# CONNECTORS.net
KiCad netlist of a schematic drawn in Altium Designer
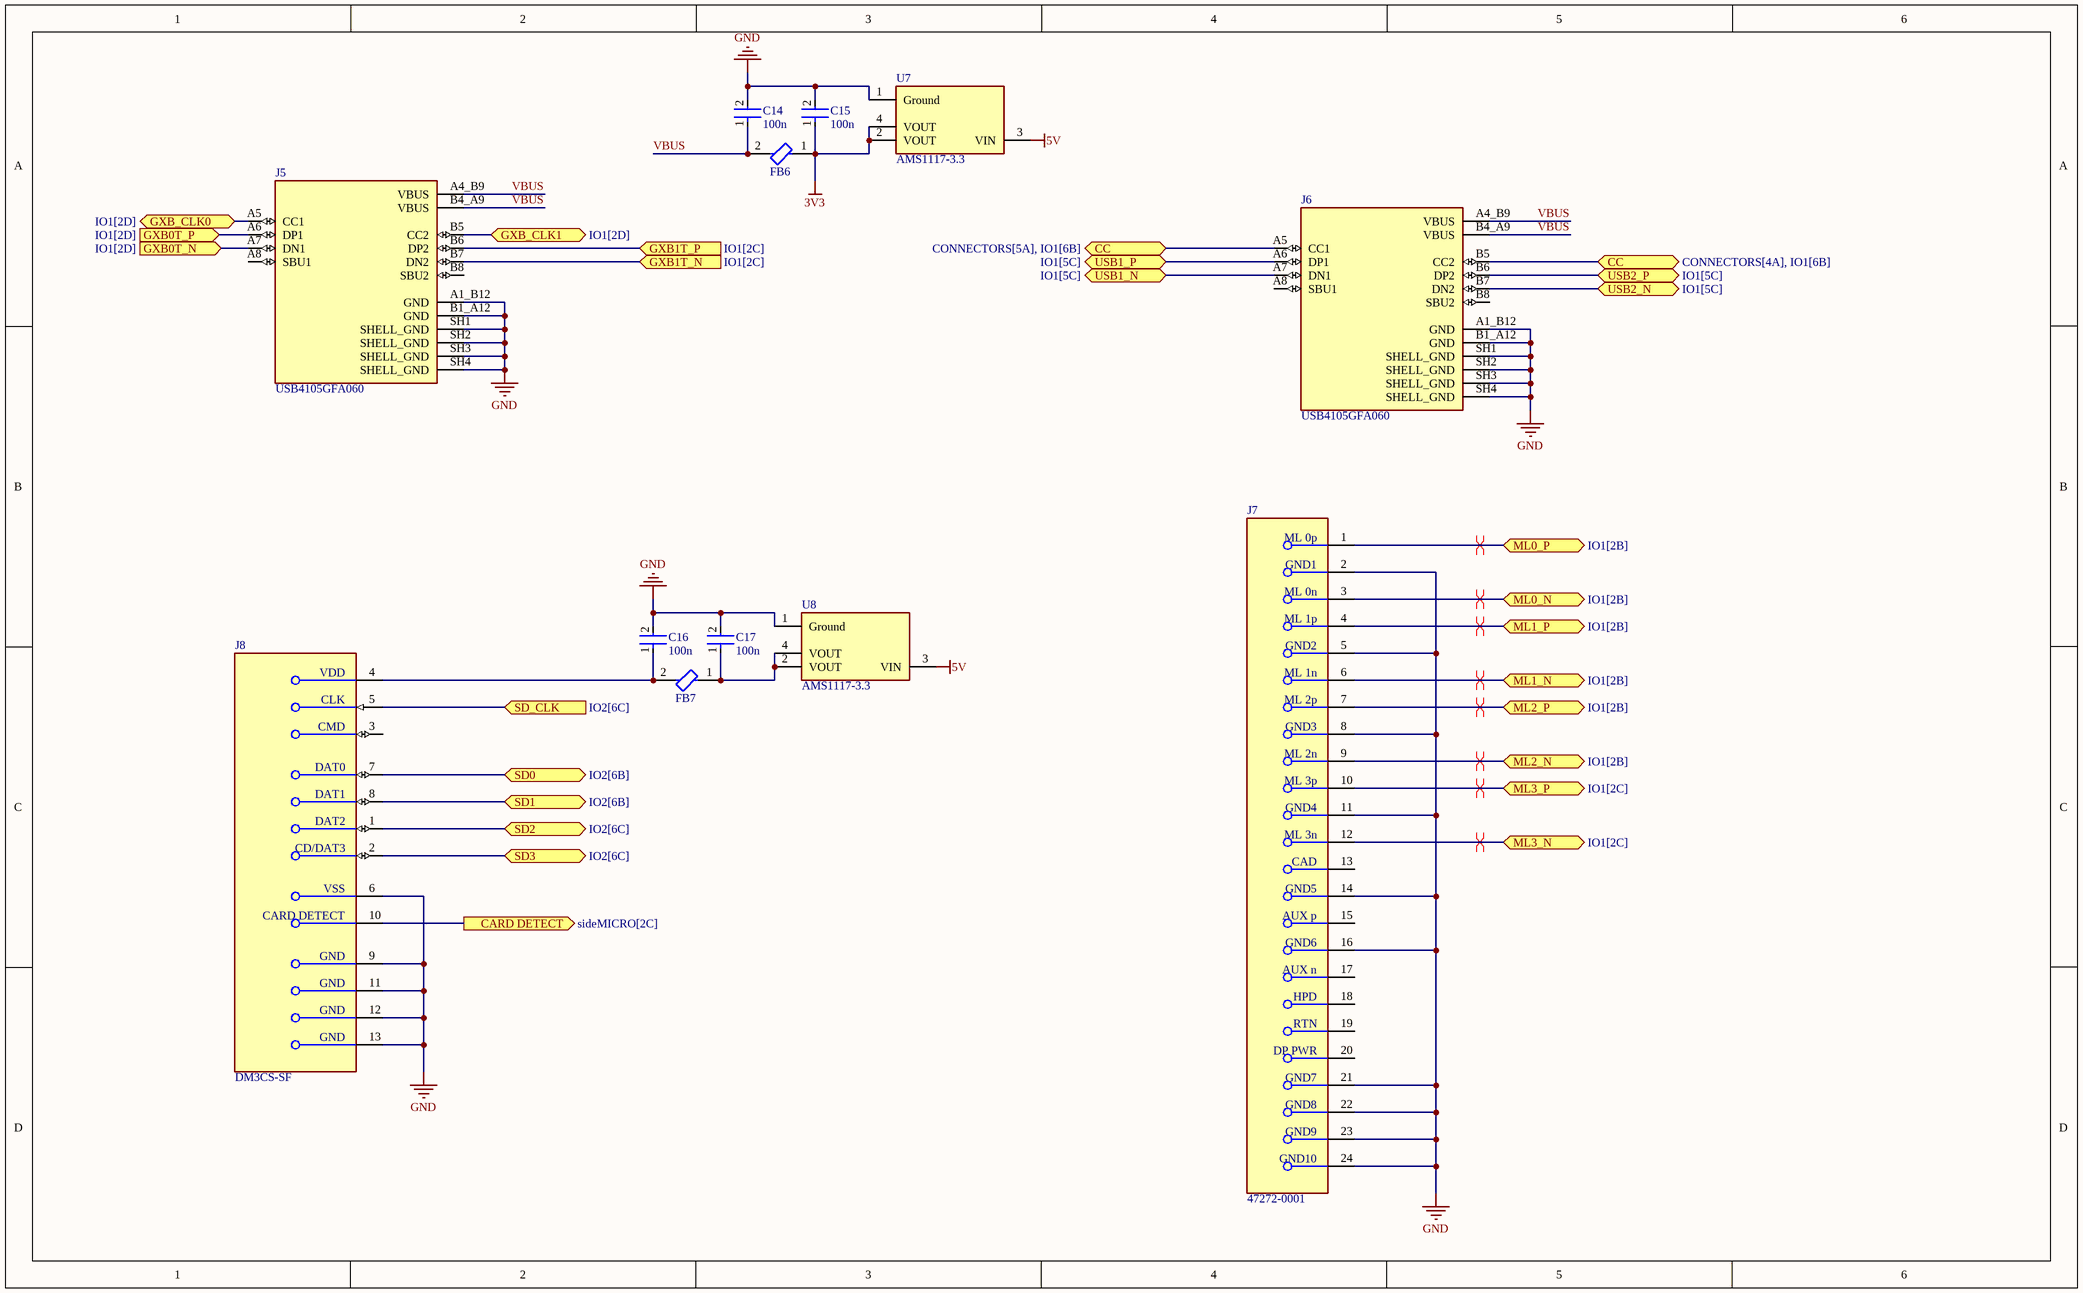
[diagram p0: CONNECTORS.SchDoc]

(export (version "E")
  (design (tool "Eeschema 10.0.6"))
  (components
    (comp (ref "C14")
      (value "100n")
      (footprint "FP-CL10-IPC_C")
      (description "Cap Ceramic 4.7uF 10V X5R ±10% Pad SMD 0603 +85°C T/R")
      (fields (field (name "TOLERANCE") "10%"))
      (libsource (lib "Altium Content Vault") (part "b4654b650e69147ec39a6b967a45e02"))
    )
    (comp (ref "C15")
      (value "100n")
      (footprint "FP-CL10-IPC_C")
      (description "Cap Ceramic 4.7uF 10V X5R ±10% Pad SMD 0603 +85°C T/R")
      (fields (field (name "TOLERANCE") "10%"))
      (libsource (lib "Altium Content Vault") (part "b4654b650e69147ec39a6b967a45e02"))
    )
    (comp (ref "C16")
      (value "100n")
      (footprint "FP-CL10-IPC_C")
      (description "Cap Ceramic 4.7uF 10V X5R ±10% Pad SMD 0603 +85°C T/R")
      (fields (field (name "TOLERANCE") "10%"))
      (libsource (lib "Altium Content Vault") (part "b4654b650e69147ec39a6b967a45e02"))
    )
    (comp (ref "C17")
      (value "100n")
      (footprint "FP-CL10-IPC_C")
      (description "Cap Ceramic 4.7uF 10V X5R ±10% Pad SMD 0603 +85°C T/R")
      (fields (field (name "TOLERANCE") "10%"))
      (libsource (lib "Altium Content Vault") (part "b4654b650e69147ec39a6b967a45e02"))
    )
    (comp (ref "FB6")
      (value "BLM18KG121TN1D")
      (footprint "FP-BLM18-0_15-t0_6-d1_2-IPC_A")
      (description "FERRITE BEAD 120 OHM 0603 1LN")
      (fields (field (name "TOLERANCE") "25%"))
      (libsource (lib "Altium Content Vault") (part "5f30dd21d616792df468990f7003faa"))
    )
    (comp (ref "FB7")
      (value "BLM18KG121TN1D")
      (footprint "FP-BLM18-0_15-t0_6-d1_2-IPC_A")
      (description "FERRITE BEAD 120 OHM 0603 1LN")
      (fields (field (name "TOLERANCE") "25%"))
      (libsource (lib "Altium Content Vault") (part "5f30dd21d616792df468990f7003faa"))
    )
    (comp (ref "J5")
      (value "USB4105GFA060")
      (footprint "GCT_USB4105GFA060")
      (fields (field (name "MF") "{'manufacturer': u'GCT'}"))
      (libsource (lib "USB4105GFA060") (part "USB4105GFA060"))
    )
    (comp (ref "J6")
      (value "USB4105GFA060")
      (footprint "GCT_USB4105GFA060")
      (fields (field (name "MF") "{'manufacturer': u'GCT'}"))
      (libsource (lib "USB4105GFA060") (part "USB4105GFA060"))
    )
    (comp (ref "J7")
      (value "47272-0001")
      (footprint "FP-47272-0001-MFG")
      (description "CONN RCPT DISPLAYPORT 20P SMD RA")
      (fields
        (field (name "MANUFACTURER") "Molex")
        (field (name "OCTOPART") "https://octopart.com/47272-0001-molex-5441289")
      )
      (libsource (lib "Altium Content Vault") (part "2afa8ceb06c8af4017661051ea5ebc1"))
    )
    (comp (ref "J8")
      (value "DM3CS-SF")
      (footprint "FP-DM3CS-SF-MFG")
      (description "CONN MICRO SD CARD HINGED TYPE")
      (libsource (lib "Altium Content Vault") (part "bac915de5305cfdd1ca301aae530106"))
    )
    (comp (ref "U7")
      (value "AMS1117-3.3")
      (footprint "FP-AMS1117-IPC_C")
      (description "LDO Voltage Regulators 1A, 3.3V")
      (fields
        (field (name "OCTOPART") "https://octopart.com/ams1117-3.3-advanced+monolithic+systems-25899300")
        (field (name "MANUFACTURER") "Advanced Monolithic Systems")
      )
      (libsource (lib "Altium Content Vault") (part "8bdbb5f8e77002000e30dd2845d0354"))
    )
    (comp (ref "U8")
      (value "AMS1117-3.3")
      (footprint "FP-AMS1117-IPC_C")
      (description "LDO Voltage Regulators 1A, 3.3V")
      (fields
        (field (name "OCTOPART") "https://octopart.com/ams1117-3.3-advanced+monolithic+systems-25899300")
        (field (name "MANUFACTURER") "Advanced Monolithic Systems")
      )
      (libsource (lib "Altium Content Vault") (part "8bdbb5f8e77002000e30dd2845d0354"))
    )
  )
  (nets
    (net (code "1") (name "/CARD DETECT") (class "Default")
      (node (ref "J8") (pin "10") (pinfunction "CARD_DETECT_10") (pintype "passive"))
    )
    (net (code "2") (name "/CC") (class "Default")
      (node (ref "J6") (pin "A5") (pinfunction "CC1_A5") (pintype "bidirectional"))
      (node (ref "J6") (pin "B5") (pinfunction "CC2_B5") (pintype "bidirectional"))
    )
    (net (code "3") (name "/GXB0T_N") (class "Default")
      (node (ref "J5") (pin "A7") (pinfunction "DN1_A7") (pintype "bidirectional"))
    )
    (net (code "4") (name "/GXB0T_P") (class "Default")
      (node (ref "J5") (pin "A6") (pinfunction "DP1_A6") (pintype "bidirectional"))
    )
    (net (code "5") (name "/GXB1T_N") (class "Default")
      (node (ref "J5") (pin "B7") (pinfunction "DN2_B7") (pintype "bidirectional"))
    )
    (net (code "6") (name "/GXB1T_P") (class "Default")
      (node (ref "J5") (pin "B6") (pinfunction "DP2_B6") (pintype "bidirectional"))
    )
    (net (code "7") (name "/GXB_CLK0") (class "Default")
      (node (ref "J5") (pin "A5") (pinfunction "CC1_A5") (pintype "bidirectional"))
    )
    (net (code "8") (name "/GXB_CLK1") (class "Default")
      (node (ref "J5") (pin "B5") (pinfunction "CC2_B5") (pintype "bidirectional"))
    )
    (net (code "9") (name "/ML0_N") (class "Default")
      (node (ref "J7") (pin "3") (pinfunction "ML_0n_3") (pintype "passive"))
    )
    (net (code "10") (name "/ML0_P") (class "Default")
      (node (ref "J7") (pin "1") (pinfunction "ML_0p_1") (pintype "passive"))
    )
    (net (code "11") (name "/ML1_N") (class "Default")
      (node (ref "J7") (pin "6") (pinfunction "ML_1n_6") (pintype "passive"))
    )
    (net (code "12") (name "/ML1_P") (class "Default")
      (node (ref "J7") (pin "4") (pinfunction "ML_1p_4") (pintype "passive"))
    )
    (net (code "13") (name "/ML2_N") (class "Default")
      (node (ref "J7") (pin "9") (pinfunction "ML_2n_9") (pintype "passive"))
    )
    (net (code "14") (name "/ML2_P") (class "Default")
      (node (ref "J7") (pin "7") (pinfunction "ML_2p_7") (pintype "passive"))
    )
    (net (code "15") (name "/ML3_N") (class "Default")
      (node (ref "J7") (pin "12") (pinfunction "ML_3n_12") (pintype "passive"))
    )
    (net (code "16") (name "/ML3_P") (class "Default")
      (node (ref "J7") (pin "10") (pinfunction "ML_3p_10") (pintype "passive"))
    )
    (net (code "17") (name "/SD0") (class "Default")
      (node (ref "J8") (pin "7") (pinfunction "DAT0_7") (pintype "bidirectional"))
    )
    (net (code "18") (name "/SD1") (class "Default")
      (node (ref "J8") (pin "8") (pinfunction "DAT1_8") (pintype "bidirectional"))
    )
    (net (code "19") (name "/SD2") (class "Default")
      (node (ref "J8") (pin "1") (pinfunction "DAT2_1") (pintype "bidirectional"))
    )
    (net (code "20") (name "/SD3") (class "Default")
      (node (ref "J8") (pin "2") (pinfunction "CD/DAT3_2") (pintype "bidirectional"))
    )
    (net (code "21") (name "/SD_CLK") (class "Default")
      (node (ref "J8") (pin "5") (pinfunction "CLK_5") (pintype "input"))
    )
    (net (code "22") (name "/USB1_N") (class "Default")
      (node (ref "J6") (pin "A7") (pinfunction "DN1_A7") (pintype "bidirectional"))
    )
    (net (code "23") (name "/USB1_P") (class "Default")
      (node (ref "J6") (pin "A6") (pinfunction "DP1_A6") (pintype "bidirectional"))
    )
    (net (code "24") (name "/USB2_N") (class "Default")
      (node (ref "J6") (pin "B7") (pinfunction "DN2_B7") (pintype "bidirectional"))
    )
    (net (code "25") (name "/USB2_P") (class "Default")
      (node (ref "J6") (pin "B6") (pinfunction "DP2_B6") (pintype "bidirectional"))
    )
    (net (code "26") (name "/VBUS") (class "Default")
      (node (ref "C14") (pin "1") (pinfunction "1_1") (pintype "passive"))
      (node (ref "FB6") (pin "2") (pinfunction "2_2") (pintype "passive"))
      (node (ref "J5") (pin "A4_B9") (pinfunction "VBUS_A4_B9") (pintype "power_in"))
      (node (ref "J5") (pin "B4_A9") (pinfunction "VBUS_B4_A9") (pintype "power_in"))
      (node (ref "J6") (pin "A4_B9") (pinfunction "VBUS_A4_B9") (pintype "power_in"))
      (node (ref "J6") (pin "B4_A9") (pinfunction "VBUS_B4_A9") (pintype "power_in"))
    )
    (net (code "27") (name "3V3") (class "Default")
      (node (ref "C15") (pin "1") (pinfunction "1_1") (pintype "passive"))
      (node (ref "FB6") (pin "1") (pinfunction "1_1") (pintype "passive"))
      (node (ref "U7") (pin "2") (pinfunction "VOUT_2") (pintype "passive"))
      (node (ref "U7") (pin "4") (pinfunction "VOUT_4") (pintype "passive"))
    )
    (net (code "28") (name "5V") (class "Default")
      (node (ref "U7") (pin "3") (pinfunction "VIN_3") (pintype "power_in"))
      (node (ref "U8") (pin "3") (pinfunction "VIN_3") (pintype "power_in"))
    )
    (net (code "29") (name "GND") (class "Default")
      (node (ref "C14") (pin "2") (pinfunction "2_2") (pintype "passive"))
      (node (ref "C15") (pin "2") (pinfunction "2_2") (pintype "passive"))
      (node (ref "C16") (pin "2") (pinfunction "2_2") (pintype "passive"))
      (node (ref "C17") (pin "2") (pinfunction "2_2") (pintype "passive"))
      (node (ref "J5") (pin "A1_B12") (pinfunction "GND_A1_B12") (pintype "power_in"))
      (node (ref "J5") (pin "B1_A12") (pinfunction "GND_B1_A12") (pintype "power_in"))
      (node (ref "J5") (pin "SH1") (pinfunction "SHELL_GND_SH1") (pintype "power_in"))
      (node (ref "J5") (pin "SH2") (pinfunction "SHELL_GND_SH2") (pintype "power_in"))
      (node (ref "J5") (pin "SH3") (pinfunction "SHELL_GND_SH3") (pintype "power_in"))
      (node (ref "J5") (pin "SH4") (pinfunction "SHELL_GND_SH4") (pintype "power_in"))
      (node (ref "J6") (pin "A1_B12") (pinfunction "GND_A1_B12") (pintype "power_in"))
      (node (ref "J6") (pin "B1_A12") (pinfunction "GND_B1_A12") (pintype "power_in"))
      (node (ref "J6") (pin "SH1") (pinfunction "SHELL_GND_SH1") (pintype "power_in"))
      (node (ref "J6") (pin "SH2") (pinfunction "SHELL_GND_SH2") (pintype "power_in"))
      (node (ref "J6") (pin "SH3") (pinfunction "SHELL_GND_SH3") (pintype "power_in"))
      (node (ref "J6") (pin "SH4") (pinfunction "SHELL_GND_SH4") (pintype "power_in"))
      (node (ref "J7") (pin "11") (pinfunction "GND4_11") (pintype "power_in"))
      (node (ref "J7") (pin "14") (pinfunction "GND5_14") (pintype "power_in"))
      (node (ref "J7") (pin "16") (pinfunction "GND6_16") (pintype "power_in"))
      (node (ref "J7") (pin "2") (pinfunction "GND1_2") (pintype "power_in"))
      (node (ref "J7") (pin "21") (pinfunction "GND7_21") (pintype "power_in"))
      (node (ref "J7") (pin "22") (pinfunction "GND8_22") (pintype "power_in"))
      (node (ref "J7") (pin "23") (pinfunction "GND9_23") (pintype "power_in"))
      (node (ref "J7") (pin "24") (pinfunction "GND10_24") (pintype "power_in"))
      (node (ref "J7") (pin "5") (pinfunction "GND2_5") (pintype "power_in"))
      (node (ref "J7") (pin "8") (pinfunction "GND3_8") (pintype "power_in"))
      (node (ref "J8") (pin "11") (pinfunction "GND_11") (pintype "power_in"))
      (node (ref "J8") (pin "12") (pinfunction "GND_12") (pintype "power_in"))
      (node (ref "J8") (pin "13") (pinfunction "GND_13") (pintype "power_in"))
      (node (ref "J8") (pin "6") (pinfunction "VSS_6") (pintype "power_in"))
      (node (ref "J8") (pin "9") (pinfunction "GND_9") (pintype "power_in"))
      (node (ref "U7") (pin "1") (pinfunction "Ground_1") (pintype "power_in"))
      (node (ref "U8") (pin "1") (pinfunction "Ground_1") (pintype "power_in"))
    )
    (net (code "30") (name "Net-(C17-Pad1)") (class "Default")
      (node (ref "C17") (pin "1") (pinfunction "1_1") (pintype "passive"))
      (node (ref "FB7") (pin "1") (pinfunction "1_1") (pintype "passive"))
      (node (ref "U8") (pin "2") (pinfunction "VOUT_2") (pintype "passive"))
      (node (ref "U8") (pin "4") (pinfunction "VOUT_4") (pintype "passive"))
    )
    (net (code "31") (name "Net-(J8-VDD)") (class "Default")
      (node (ref "C16") (pin "1") (pinfunction "1_1") (pintype "passive"))
      (node (ref "FB7") (pin "2") (pinfunction "2_2") (pintype "passive"))
      (node (ref "J8") (pin "4") (pinfunction "VDD_4") (pintype "power_in"))
    )
    (net (code "32") (name "unconnected-(J5-SBU1-PadA8)") (class "Default")
      (node (ref "J5") (pin "A8") (pinfunction "SBU1_A8") (pintype "bidirectional"))
    )
    (net (code "33") (name "unconnected-(J5-SBU2-PadB8)") (class "Default")
      (node (ref "J5") (pin "B8") (pinfunction "SBU2_B8") (pintype "bidirectional"))
    )
    (net (code "34") (name "unconnected-(J6-SBU1-PadA8)") (class "Default")
      (node (ref "J6") (pin "A8") (pinfunction "SBU1_A8") (pintype "bidirectional"))
    )
    (net (code "35") (name "unconnected-(J6-SBU2-PadB8)") (class "Default")
      (node (ref "J6") (pin "B8") (pinfunction "SBU2_B8") (pintype "bidirectional"))
    )
    (net (code "36") (name "unconnected-(J7-AUX_n-Pad17)") (class "Default")
      (node (ref "J7") (pin "17") (pinfunction "AUX_n_17") (pintype "passive"))
    )
    (net (code "37") (name "unconnected-(J7-AUX_p-Pad15)") (class "Default")
      (node (ref "J7") (pin "15") (pinfunction "AUX_p_15") (pintype "passive"))
    )
    (net (code "38") (name "unconnected-(J7-CAD-Pad13)") (class "Default")
      (node (ref "J7") (pin "13") (pinfunction "CAD_13") (pintype "passive"))
    )
    (net (code "39") (name "unconnected-(J7-DP_PWR-Pad20)") (class "Default")
      (node (ref "J7") (pin "20") (pinfunction "DP_PWR_20") (pintype "passive"))
    )
    (net (code "40") (name "unconnected-(J7-HPD-Pad18)") (class "Default")
      (node (ref "J7") (pin "18") (pinfunction "HPD_18") (pintype "passive"))
    )
    (net (code "41") (name "unconnected-(J7-RTN-Pad19)") (class "Default")
      (node (ref "J7") (pin "19") (pinfunction "RTN_19") (pintype "passive"))
    )
    (net (code "42") (name "unconnected-(J8-CMD-Pad3)") (class "Default")
      (node (ref "J8") (pin "3") (pinfunction "CMD_3") (pintype "bidirectional"))
    )
  )
)
